# DAC.net
KiCad netlist of a schematic drawn in Altium Designer
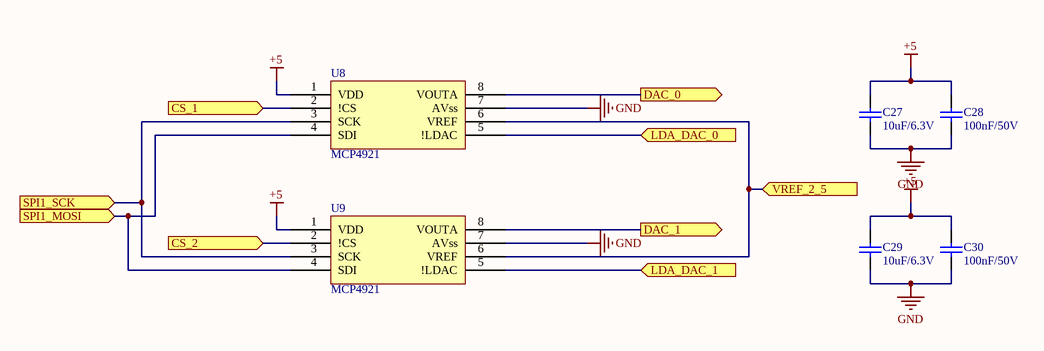
[diagram p0: DAC.SchDoc]

(export (version "E")
  (design (tool "Eeschema 10.0.6"))
  (components
    (comp (ref "C27")
      (value "10uF/6.3V")
      (footprint "CAP_0805")
      (libsource (lib "Iot_Flatform_lib_PTT") (part "Capacitor"))
    )
    (comp (ref "C28")
      (value "100nF/50V")
      (footprint "CAP_0805")
      (libsource (lib "Iot_Flatform_lib_PTT") (part "Capacitor"))
    )
    (comp (ref "C29")
      (value "10uF/6.3V")
      (footprint "CAP_0805")
      (libsource (lib "Iot_Flatform_lib_PTT") (part "Capacitor"))
    )
    (comp (ref "C30")
      (value "100nF/50V")
      (footprint "CAP_0805")
      (libsource (lib "Iot_Flatform_lib_PTT") (part "Capacitor"))
    )
    (comp (ref "U8")
      (value "MCP4921")
      (footprint "SOIC127P600X175-8N")
      (description "Interface SPI")
      (libsource (lib "Iot_Flatform_lib_PTT") (part "MCP4921"))
    )
    (comp (ref "U9")
      (value "MCP4921")
      (footprint "SOIC127P600X175-8N")
      (description "Interface SPI")
      (libsource (lib "Iot_Flatform_lib_PTT") (part "MCP4921"))
    )
  )
  (nets
    (net (code "1") (name "+5") (class "Default")
      (node (ref "C27") (pin "2") (pinfunction "2_2") (pintype "passive"))
      (node (ref "C28") (pin "2") (pinfunction "2_2") (pintype "passive"))
      (node (ref "C29") (pin "2") (pinfunction "2_2") (pintype "passive"))
      (node (ref "C30") (pin "2") (pinfunction "2_2") (pintype "passive"))
      (node (ref "U8") (pin "1") (pinfunction "VDD_1") (pintype "passive"))
      (node (ref "U9") (pin "1") (pinfunction "VDD_1") (pintype "passive"))
    )
    (net (code "2") (name "/CS_1") (class "Default")
      (node (ref "U8") (pin "2") (pinfunction "!CS_2") (pintype "passive"))
    )
    (net (code "3") (name "/CS_2") (class "Default")
      (node (ref "U9") (pin "2") (pinfunction "!CS_2") (pintype "passive"))
    )
    (net (code "4") (name "/DAC_0") (class "Default")
      (node (ref "U8") (pin "8") (pinfunction "VOUTA_8") (pintype "passive"))
    )
    (net (code "5") (name "/DAC_1") (class "Default")
      (node (ref "U9") (pin "8") (pinfunction "VOUTA_8") (pintype "passive"))
    )
    (net (code "6") (name "/LDA_DAC_0") (class "Default")
      (node (ref "U8") (pin "5") (pinfunction "!LDAC_5") (pintype "passive"))
    )
    (net (code "7") (name "/LDA_DAC_1") (class "Default")
      (node (ref "U9") (pin "5") (pinfunction "!LDAC_5") (pintype "passive"))
    )
    (net (code "8") (name "/SPI1_MOSI") (class "Default")
      (node (ref "U8") (pin "4") (pinfunction "SDI_4") (pintype "passive"))
      (node (ref "U9") (pin "4") (pinfunction "SDI_4") (pintype "passive"))
    )
    (net (code "9") (name "/SPI1_SCK") (class "Default")
      (node (ref "U8") (pin "3") (pinfunction "SCK_3") (pintype "passive"))
      (node (ref "U9") (pin "3") (pinfunction "SCK_3") (pintype "passive"))
    )
    (net (code "10") (name "/VREF_2_5") (class "Default")
      (node (ref "U8") (pin "6") (pinfunction "VREF_6") (pintype "passive"))
      (node (ref "U9") (pin "6") (pinfunction "VREF_6") (pintype "passive"))
    )
    (net (code "11") (name "GND") (class "Default")
      (node (ref "C27") (pin "1") (pinfunction "1_1") (pintype "passive"))
      (node (ref "C28") (pin "1") (pinfunction "1_1") (pintype "passive"))
      (node (ref "C29") (pin "1") (pinfunction "1_1") (pintype "passive"))
      (node (ref "C30") (pin "1") (pinfunction "1_1") (pintype "passive"))
      (node (ref "U8") (pin "7") (pinfunction "AVss_7") (pintype "passive"))
      (node (ref "U9") (pin "7") (pinfunction "AVss_7") (pintype "passive"))
    )
  )
)
